# PiDGC.net
KiCad netlist of a schematic drawn in EAGLE
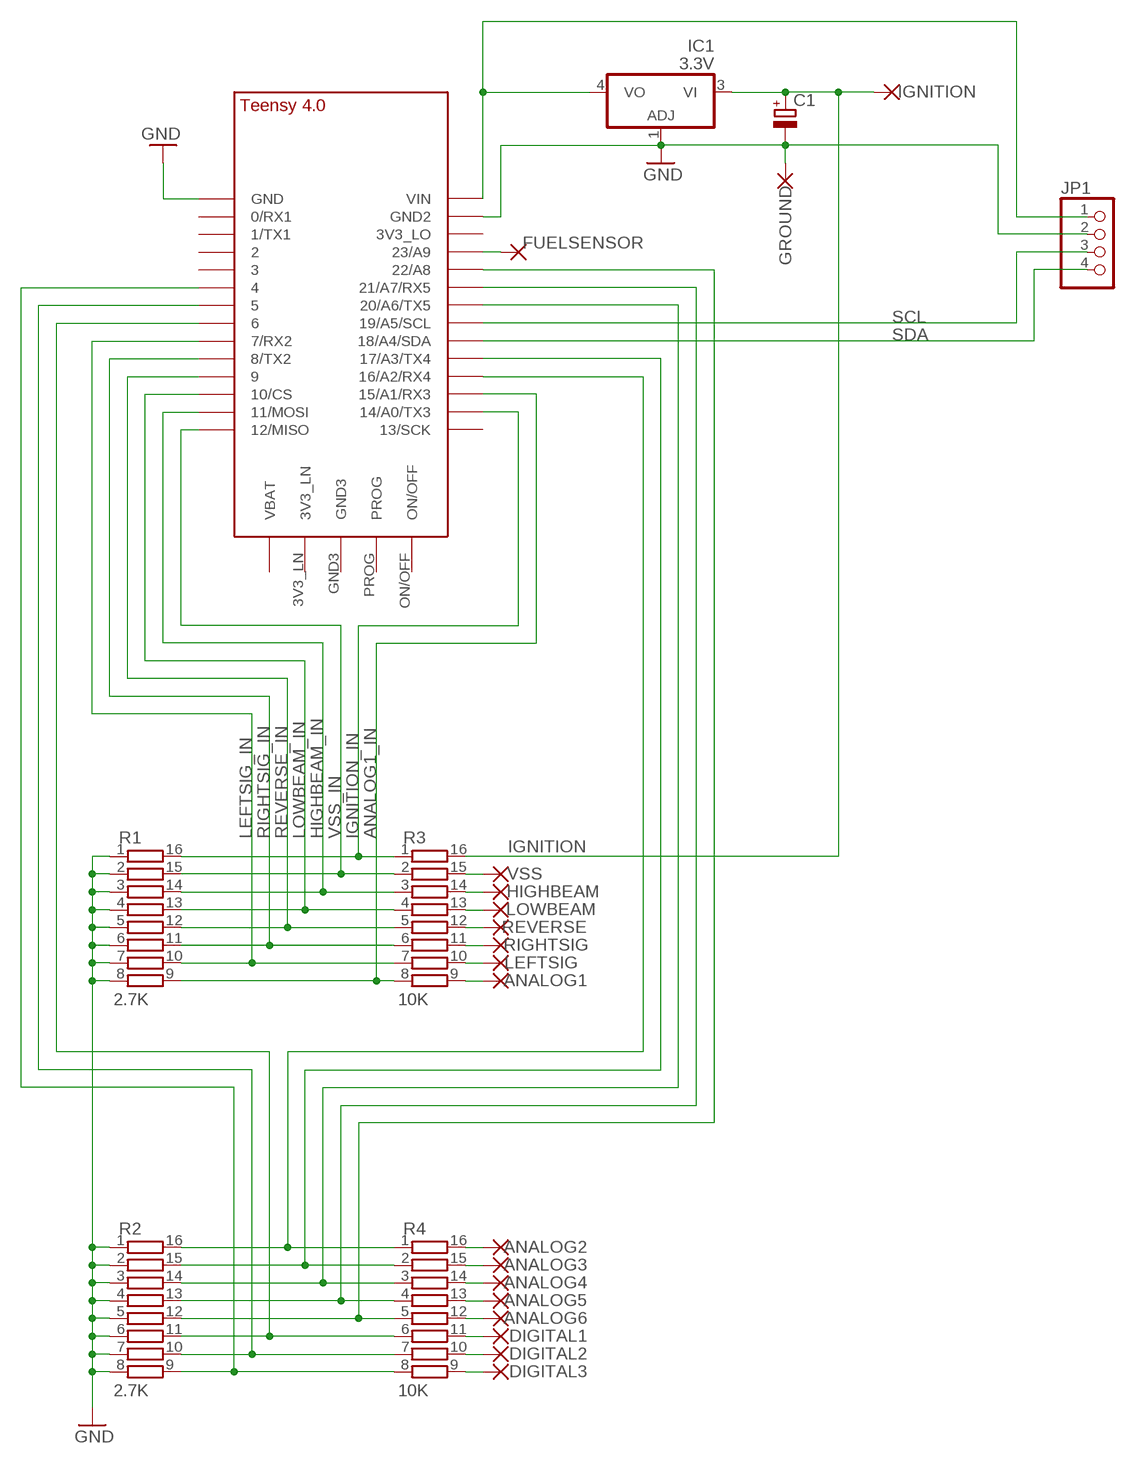
[diagram p0: schematic, sheet 1]

(export (version "E")
  (design (tool "Eeschema 10.0.6"))
  (components
    (comp (ref "ANALOG1")
      (value "WIREPAD3,81/1,4")
      (footprint "eagle-import:3,81_1,4")
      (libsource (lib "eagle-import") (part "WIREPAD3,81/1,4"))
    )
    (comp (ref "ANALOG2")
      (value "WIREPAD3,81/1,4")
      (footprint "eagle-import:3,81_1,4")
      (libsource (lib "eagle-import") (part "WIREPAD3,81/1,4"))
    )
    (comp (ref "ANALOG3")
      (value "WIREPAD3,81/1,4")
      (footprint "eagle-import:3,81_1,4")
      (libsource (lib "eagle-import") (part "WIREPAD3,81/1,4"))
    )
    (comp (ref "ANALOG4")
      (value "WIREPAD3,81/1,4")
      (footprint "eagle-import:3,81_1,4")
      (libsource (lib "eagle-import") (part "WIREPAD3,81/1,4"))
    )
    (comp (ref "ANALOG5")
      (value "WIREPAD3,81/1,4")
      (footprint "eagle-import:3,81_1,4")
      (libsource (lib "eagle-import") (part "WIREPAD3,81/1,4"))
    )
    (comp (ref "ANALOG6")
      (value "WIREPAD3,81/1,4")
      (footprint "eagle-import:3,81_1,4")
      (libsource (lib "eagle-import") (part "WIREPAD3,81/1,4"))
    )
    (comp (ref "C1")
      (value "CPOL-EUE7.5-16")
      (footprint "eagle-import:E7,5-16")
      (libsource (lib "eagle-import") (part "CPOL-EUE7.5-16"))
    )
    (comp (ref "DIGITAL1")
      (value "WIREPAD3,81/1,4")
      (footprint "eagle-import:3,81_1,4")
      (libsource (lib "eagle-import") (part "WIREPAD3,81/1,4"))
    )
    (comp (ref "DIGITAL2")
      (value "WIREPAD3,81/1,4")
      (footprint "eagle-import:3,81_1,4")
      (libsource (lib "eagle-import") (part "WIREPAD3,81/1,4"))
    )
    (comp (ref "DIGITAL3")
      (value "WIREPAD3,81/1,4")
      (footprint "eagle-import:3,81_1,4")
      (libsource (lib "eagle-import") (part "WIREPAD3,81/1,4"))
    )
    (comp (ref "FUELSENSOR")
      (value "WIREPAD3,81/1,4")
      (footprint "eagle-import:3,81_1,4")
      (libsource (lib "eagle-import") (part "WIREPAD3,81/1,4"))
    )
    (comp (ref "GROUND")
      (value "WIREPAD3,81/1,4")
      (footprint "eagle-import:3,81_1,4")
      (libsource (lib "eagle-import") (part "WIREPAD3,81/1,4"))
    )
    (comp (ref "HIGHBEAM")
      (value "WIREPAD3,81/1,4")
      (footprint "eagle-import:3,81_1,4")
      (libsource (lib "eagle-import") (part "WIREPAD3,81/1,4"))
    )
    (comp (ref "IC1")
      (value "3.3V")
      (footprint "eagle-import:SOT223")
      (libsource (lib "eagle-import") (part "317EMP"))
    )
    (comp (ref "IGNITION")
      (value "WIREPAD3,81/1,4")
      (footprint "eagle-import:3,81_1,4")
      (libsource (lib "eagle-import") (part "WIREPAD3,81/1,4"))
    )
    (comp (ref "JP1")
      (value "PINHD-1X4")
      (footprint "eagle-import:1X04")
      (libsource (lib "eagle-import") (part "PINHD-1X4"))
    )
    (comp (ref "LEFTSIG")
      (value "WIREPAD3,81/1,4")
      (footprint "eagle-import:3,81_1,4")
      (libsource (lib "eagle-import") (part "WIREPAD3,81/1,4"))
    )
    (comp (ref "LOWBEAM")
      (value "WIREPAD3,81/1,4")
      (footprint "eagle-import:3,81_1,4")
      (libsource (lib "eagle-import") (part "WIREPAD3,81/1,4"))
    )
    (comp (ref "R1")
      (value "2.7K")
      (footprint "eagle-import:SO16")
      (libsource (lib "eagle-import") (part "2NBS16-8"))
    )
    (comp (ref "R2")
      (value "2.7K")
      (footprint "eagle-import:SO16")
      (libsource (lib "eagle-import") (part "2NBS16-8"))
    )
    (comp (ref "R3")
      (value "10K")
      (footprint "eagle-import:SO16")
      (libsource (lib "eagle-import") (part "2NBS16-8"))
    )
    (comp (ref "R4")
      (value "10K")
      (footprint "eagle-import:SO16")
      (libsource (lib "eagle-import") (part "2NBS16-8"))
    )
    (comp (ref "REVERSE")
      (value "WIREPAD3,81/1,4")
      (footprint "eagle-import:3,81_1,4")
      (libsource (lib "eagle-import") (part "WIREPAD3,81/1,4"))
    )
    (comp (ref "RIGHTSIG")
      (value "WIREPAD3,81/1,4")
      (footprint "eagle-import:3,81_1,4")
      (libsource (lib "eagle-import") (part "WIREPAD3,81/1,4"))
    )
    (comp (ref "U$1")
      (value "TEENSY_4.0")
      (footprint "eagle-import:TEENSY_4.0")
      (libsource (lib "eagle-import") (part "TEENSY_4.0"))
    )
    (comp (ref "VSS")
      (value "WIREPAD3,81/1,4")
      (footprint "eagle-import:3,81_1,4")
      (libsource (lib "eagle-import") (part "WIREPAD3,81/1,4"))
    )
  )
  (nets
    (net (code "1") (name "/ANALOG1_IN") (class "Default")
      (node (ref "R1") (pin "9") (pinfunction "9_9") (pintype "passive"))
      (node (ref "R3") (pin "8") (pinfunction "8_8") (pintype "passive"))
      (node (ref "U$1") (pin "15/A1") (pinfunction "15/A1/RX3_15/A1") (pintype "bidirectional"))
    )
    (net (code "2") (name "/HIGHBEAM_IN") (class "Default")
      (node (ref "R1") (pin "14") (pinfunction "14_14") (pintype "passive"))
      (node (ref "R3") (pin "3") (pinfunction "3_3") (pintype "passive"))
      (node (ref "U$1") (pin "11/MOSI") (pinfunction "11/MOSI_11/MOSI") (pintype "bidirectional"))
    )
    (net (code "3") (name "/IGNITION") (class "Default")
      (node (ref "C1") (pin "+") (pinfunction "+_+") (pintype "passive"))
      (node (ref "IC1") (pin "3") (pinfunction "VI_3") (pintype "input"))
      (node (ref "IGNITION") (pin "1") (pinfunction "P_1") (pintype "passive"))
      (node (ref "R3") (pin "16") (pinfunction "16_16") (pintype "passive"))
    )
    (net (code "4") (name "/IGNITION_IN") (class "Default")
      (node (ref "R1") (pin "16") (pinfunction "16_16") (pintype "passive"))
      (node (ref "R3") (pin "1") (pinfunction "1_1") (pintype "passive"))
      (node (ref "U$1") (pin "14/A0") (pinfunction "14/A0/TX3_14/A0") (pintype "bidirectional"))
    )
    (net (code "5") (name "/LEFTSIG_IN") (class "Default")
      (node (ref "R1") (pin "10") (pinfunction "10_10") (pintype "passive"))
      (node (ref "R3") (pin "7") (pinfunction "7_7") (pintype "passive"))
      (node (ref "U$1") (pin "7") (pinfunction "7/RX2_7") (pintype "bidirectional"))
    )
    (net (code "6") (name "/LOWBEAM_IN") (class "Default")
      (node (ref "R1") (pin "13") (pinfunction "13_13") (pintype "passive"))
      (node (ref "R3") (pin "4") (pinfunction "4_4") (pintype "passive"))
      (node (ref "U$1") (pin "10/CS") (pinfunction "10/CS_10/CS") (pintype "bidirectional"))
    )
    (net (code "7") (name "/REVERSE_IN") (class "Default")
      (node (ref "R1") (pin "12") (pinfunction "12_12") (pintype "passive"))
      (node (ref "R3") (pin "5") (pinfunction "5_5") (pintype "passive"))
      (node (ref "U$1") (pin "9/CS") (pinfunction "9_9/CS") (pintype "bidirectional"))
    )
    (net (code "8") (name "/RIGHTSIG_IN") (class "Default")
      (node (ref "R1") (pin "11") (pinfunction "11_11") (pintype "passive"))
      (node (ref "R3") (pin "6") (pinfunction "6_6") (pintype "passive"))
      (node (ref "U$1") (pin "8") (pinfunction "8/TX2_8") (pintype "bidirectional"))
    )
    (net (code "9") (name "/SCL") (class "Default")
      (node (ref "JP1") (pin "3") (pinfunction "3_3") (pintype "passive"))
      (node (ref "U$1") (pin "19/A5/SCL") (pinfunction "19/A5/SCL_19/A5/SCL") (pintype "bidirectional"))
    )
    (net (code "10") (name "/SDA") (class "Default")
      (node (ref "JP1") (pin "4") (pinfunction "4_4") (pintype "passive"))
      (node (ref "U$1") (pin "18/A4/SDA") (pinfunction "18/A4/SDA_18/A4/SDA") (pintype "bidirectional"))
    )
    (net (code "11") (name "/VSS_IN") (class "Default")
      (node (ref "R1") (pin "15") (pinfunction "15_15") (pintype "passive"))
      (node (ref "R3") (pin "2") (pinfunction "2_2") (pintype "passive"))
      (node (ref "U$1") (pin "12/MISO") (pinfunction "12/MISO_12/MISO") (pintype "bidirectional"))
    )
    (net (code "12") (name "GND") (class "Default")
      (node (ref "C1") (pin "-") (pinfunction "-_-") (pintype "passive"))
      (node (ref "GROUND") (pin "1") (pinfunction "P_1") (pintype "passive"))
      (node (ref "IC1") (pin "1") (pinfunction "ADJ_1") (pintype "input"))
      (node (ref "JP1") (pin "2") (pinfunction "2_2") (pintype "passive"))
      (node (ref "R1") (pin "1") (pinfunction "1_1") (pintype "passive"))
      (node (ref "R1") (pin "2") (pinfunction "2_2") (pintype "passive"))
      (node (ref "R1") (pin "3") (pinfunction "3_3") (pintype "passive"))
      (node (ref "R1") (pin "4") (pinfunction "4_4") (pintype "passive"))
      (node (ref "R1") (pin "5") (pinfunction "5_5") (pintype "passive"))
      (node (ref "R1") (pin "6") (pinfunction "6_6") (pintype "passive"))
      (node (ref "R1") (pin "7") (pinfunction "7_7") (pintype "passive"))
      (node (ref "R1") (pin "8") (pinfunction "8_8") (pintype "passive"))
      (node (ref "R2") (pin "1") (pinfunction "1_1") (pintype "passive"))
      (node (ref "R2") (pin "2") (pinfunction "2_2") (pintype "passive"))
      (node (ref "R2") (pin "3") (pinfunction "3_3") (pintype "passive"))
      (node (ref "R2") (pin "4") (pinfunction "4_4") (pintype "passive"))
      (node (ref "R2") (pin "5") (pinfunction "5_5") (pintype "passive"))
      (node (ref "R2") (pin "6") (pinfunction "6_6") (pintype "passive"))
      (node (ref "R2") (pin "7") (pinfunction "7_7") (pintype "passive"))
      (node (ref "R2") (pin "8") (pinfunction "8_8") (pintype "passive"))
      (node (ref "U$1") (pin "GND") (pinfunction "GND_GND") (pintype "bidirectional"))
      (node (ref "U$1") (pin "GND2") (pinfunction "GND2_GND2") (pintype "bidirectional"))
    )
    (net (code "13") (name "Net-(ANALOG1-P)") (class "Default")
      (node (ref "ANALOG1") (pin "1") (pinfunction "P_1") (pintype "passive"))
      (node (ref "R3") (pin "9") (pinfunction "9_9") (pintype "passive"))
    )
    (net (code "14") (name "Net-(ANALOG2-P)") (class "Default")
      (node (ref "ANALOG2") (pin "1") (pinfunction "P_1") (pintype "passive"))
      (node (ref "R4") (pin "16") (pinfunction "16_16") (pintype "passive"))
    )
    (net (code "15") (name "Net-(ANALOG3-P)") (class "Default")
      (node (ref "ANALOG3") (pin "1") (pinfunction "P_1") (pintype "passive"))
      (node (ref "R4") (pin "15") (pinfunction "15_15") (pintype "passive"))
    )
    (net (code "16") (name "Net-(ANALOG4-P)") (class "Default")
      (node (ref "ANALOG4") (pin "1") (pinfunction "P_1") (pintype "passive"))
      (node (ref "R4") (pin "14") (pinfunction "14_14") (pintype "passive"))
    )
    (net (code "17") (name "Net-(ANALOG5-P)") (class "Default")
      (node (ref "ANALOG5") (pin "1") (pinfunction "P_1") (pintype "passive"))
      (node (ref "R4") (pin "13") (pinfunction "13_13") (pintype "passive"))
    )
    (net (code "18") (name "Net-(ANALOG6-P)") (class "Default")
      (node (ref "ANALOG6") (pin "1") (pinfunction "P_1") (pintype "passive"))
      (node (ref "R4") (pin "12") (pinfunction "12_12") (pintype "passive"))
    )
    (net (code "19") (name "Net-(DIGITAL1-P)") (class "Default")
      (node (ref "DIGITAL1") (pin "1") (pinfunction "P_1") (pintype "passive"))
      (node (ref "R4") (pin "11") (pinfunction "11_11") (pintype "passive"))
    )
    (net (code "20") (name "Net-(DIGITAL2-P)") (class "Default")
      (node (ref "DIGITAL2") (pin "1") (pinfunction "P_1") (pintype "passive"))
      (node (ref "R4") (pin "10") (pinfunction "10_10") (pintype "passive"))
    )
    (net (code "21") (name "Net-(DIGITAL3-P)") (class "Default")
      (node (ref "DIGITAL3") (pin "1") (pinfunction "P_1") (pintype "passive"))
      (node (ref "R4") (pin "9") (pinfunction "9_9") (pintype "passive"))
    )
    (net (code "22") (name "Net-(FUELSENSOR-P)") (class "Default")
      (node (ref "FUELSENSOR") (pin "1") (pinfunction "P_1") (pintype "passive"))
      (node (ref "U$1") (pin "23/A9") (pinfunction "23/A9_23/A9") (pintype "bidirectional"))
    )
    (net (code "23") (name "Net-(HIGHBEAM-P)") (class "Default")
      (node (ref "HIGHBEAM") (pin "1") (pinfunction "P_1") (pintype "passive"))
      (node (ref "R3") (pin "14") (pinfunction "14_14") (pintype "passive"))
    )
    (net (code "24") (name "Net-(IC1-VO)") (class "Default")
      (node (ref "IC1") (pin "4") (pinfunction "VO_4") (pintype "passive"))
      (node (ref "JP1") (pin "1") (pinfunction "1_1") (pintype "passive"))
      (node (ref "U$1") (pin "VIN") (pinfunction "VIN_VIN") (pintype "bidirectional"))
    )
    (net (code "25") (name "Net-(LEFTSIG-P)") (class "Default")
      (node (ref "LEFTSIG") (pin "1") (pinfunction "P_1") (pintype "passive"))
      (node (ref "R3") (pin "10") (pinfunction "10_10") (pintype "passive"))
    )
    (net (code "26") (name "Net-(LOWBEAM-P)") (class "Default")
      (node (ref "LOWBEAM") (pin "1") (pinfunction "P_1") (pintype "passive"))
      (node (ref "R3") (pin "13") (pinfunction "13_13") (pintype "passive"))
    )
    (net (code "27") (name "Net-(R2-Pad10)") (class "Default")
      (node (ref "R2") (pin "10") (pinfunction "10_10") (pintype "passive"))
      (node (ref "R4") (pin "7") (pinfunction "7_7") (pintype "passive"))
      (node (ref "U$1") (pin "5") (pinfunction "5_5") (pintype "bidirectional"))
    )
    (net (code "28") (name "Net-(R2-Pad11)") (class "Default")
      (node (ref "R2") (pin "11") (pinfunction "11_11") (pintype "passive"))
      (node (ref "R4") (pin "6") (pinfunction "6_6") (pintype "passive"))
      (node (ref "U$1") (pin "6") (pinfunction "6_6") (pintype "bidirectional"))
    )
    (net (code "29") (name "Net-(R2-Pad12)") (class "Default")
      (node (ref "R2") (pin "12") (pinfunction "12_12") (pintype "passive"))
      (node (ref "R4") (pin "5") (pinfunction "5_5") (pintype "passive"))
      (node (ref "U$1") (pin "22/A8") (pinfunction "22/A8_22/A8") (pintype "bidirectional"))
    )
    (net (code "30") (name "Net-(REVERSE-P)") (class "Default")
      (node (ref "R3") (pin "12") (pinfunction "12_12") (pintype "passive"))
      (node (ref "REVERSE") (pin "1") (pinfunction "P_1") (pintype "passive"))
    )
    (net (code "31") (name "Net-(RIGHTSIG-P)") (class "Default")
      (node (ref "R3") (pin "11") (pinfunction "11_11") (pintype "passive"))
      (node (ref "RIGHTSIG") (pin "1") (pinfunction "P_1") (pintype "passive"))
    )
    (net (code "32") (name "Net-(U$1-4)") (class "Default")
      (node (ref "R2") (pin "9") (pinfunction "9_9") (pintype "passive"))
      (node (ref "R4") (pin "8") (pinfunction "8_8") (pintype "passive"))
      (node (ref "U$1") (pin "4/CANRX") (pinfunction "4_4/CANRX") (pintype "bidirectional"))
    )
    (net (code "33") (name "Net-(U$1-16{slash}A2{slash}RX4)") (class "Default")
      (node (ref "R2") (pin "16") (pinfunction "16_16") (pintype "passive"))
      (node (ref "R4") (pin "1") (pinfunction "1_1") (pintype "passive"))
      (node (ref "U$1") (pin "16/A2") (pinfunction "16/A2/RX4_16/A2") (pintype "bidirectional"))
    )
    (net (code "34") (name "Net-(U$1-17{slash}A3{slash}TX4)") (class "Default")
      (node (ref "R2") (pin "15") (pinfunction "15_15") (pintype "passive"))
      (node (ref "R4") (pin "2") (pinfunction "2_2") (pintype "passive"))
      (node (ref "U$1") (pin "17/A3") (pinfunction "17/A3/TX4_17/A3") (pintype "bidirectional"))
    )
    (net (code "35") (name "Net-(U$1-20{slash}A6{slash}TX5)") (class "Default")
      (node (ref "R2") (pin "14") (pinfunction "14_14") (pintype "passive"))
      (node (ref "R4") (pin "3") (pinfunction "3_3") (pintype "passive"))
      (node (ref "U$1") (pin "20/A6") (pinfunction "20/A6/TX5_20/A6") (pintype "bidirectional"))
    )
    (net (code "36") (name "Net-(U$1-21{slash}A7{slash}RX5)") (class "Default")
      (node (ref "R2") (pin "13") (pinfunction "13_13") (pintype "passive"))
      (node (ref "R4") (pin "4") (pinfunction "4_4") (pintype "passive"))
      (node (ref "U$1") (pin "21/A7") (pinfunction "21/A7/RX5_21/A7") (pintype "bidirectional"))
    )
    (net (code "37") (name "Net-(VSS-P)") (class "Default")
      (node (ref "R3") (pin "15") (pinfunction "15_15") (pintype "passive"))
      (node (ref "VSS") (pin "1") (pinfunction "P_1") (pintype "passive"))
    )
    (net (code "38") (name "unconnected-(U$1-0{slash}RX1-Pad0{slash}RX)") (class "Default")
      (node (ref "U$1") (pin "0/RX") (pinfunction "0/RX1_0/RX") (pintype "bidirectional"))
    )
    (net (code "39") (name "unconnected-(U$1-1{slash}TX1-Pad1{slash}TX)") (class "Default")
      (node (ref "U$1") (pin "1/TX") (pinfunction "1/TX1_1/TX") (pintype "bidirectional"))
    )
    (net (code "40") (name "unconnected-(U$1-3-Pad3{slash}CANTX)") (class "Default")
      (node (ref "U$1") (pin "3/CANTX") (pinfunction "3_3/CANTX") (pintype "bidirectional"))
    )
    (net (code "41") (name "unconnected-(U$1-Pad2)") (class "Default")
      (node (ref "U$1") (pin "2") (pinfunction "2_2") (pintype "bidirectional"))
    )
    (net (code "42") (name "unconnected-(U$1-Pad3V3_LN)") (class "Default")
      (node (ref "U$1") (pin "3V3_LN") (pinfunction "3V3_LN_3V3_LN") (pintype "bidirectional"))
    )
    (net (code "43") (name "unconnected-(U$1-Pad3V3_LO)") (class "Default")
      (node (ref "U$1") (pin "3V3_LO") (pinfunction "3V3_LO_3V3_LO") (pintype "bidirectional"))
    )
    (net (code "44") (name "unconnected-(U$1-Pad13{slash}SCK)") (class "Default")
      (node (ref "U$1") (pin "13/SCK") (pinfunction "13/SCK_13/SCK") (pintype "bidirectional"))
    )
    (net (code "45") (name "unconnected-(U$1-PadGND3)") (class "Default")
      (node (ref "U$1") (pin "GND3") (pinfunction "GND3_GND3") (pintype "bidirectional"))
    )
    (net (code "46") (name "unconnected-(U$1-PadON{slash}OFF)") (class "Default")
      (node (ref "U$1") (pin "ON/OFF") (pinfunction "ON/OFF_ON/OFF") (pintype "bidirectional"))
    )
    (net (code "47") (name "unconnected-(U$1-PadPROG)") (class "Default")
      (node (ref "U$1") (pin "PROG") (pinfunction "PROG_PROG") (pintype "bidirectional"))
    )
    (net (code "48") (name "unconnected-(U$1-VBAT-PadVBAT\\)") (class "Default")
      (node (ref "U$1") (pin "VBAT\\") (pinfunction "VBAT_VBAT\\") (pintype "bidirectional"))
    )
  )
)
